# McPiFace-RGBPanel-V1.net
KiCad netlist of a schematic drawn in EAGLE
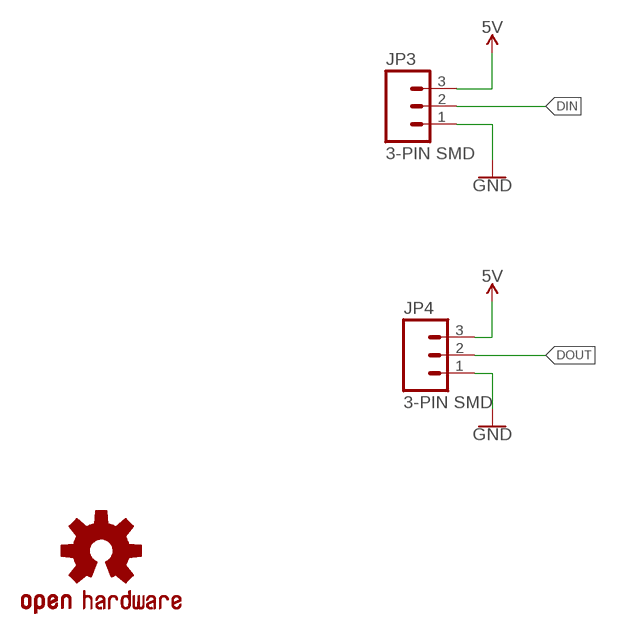
[diagram p0: schematic, sheet 1, part 1 of 2]
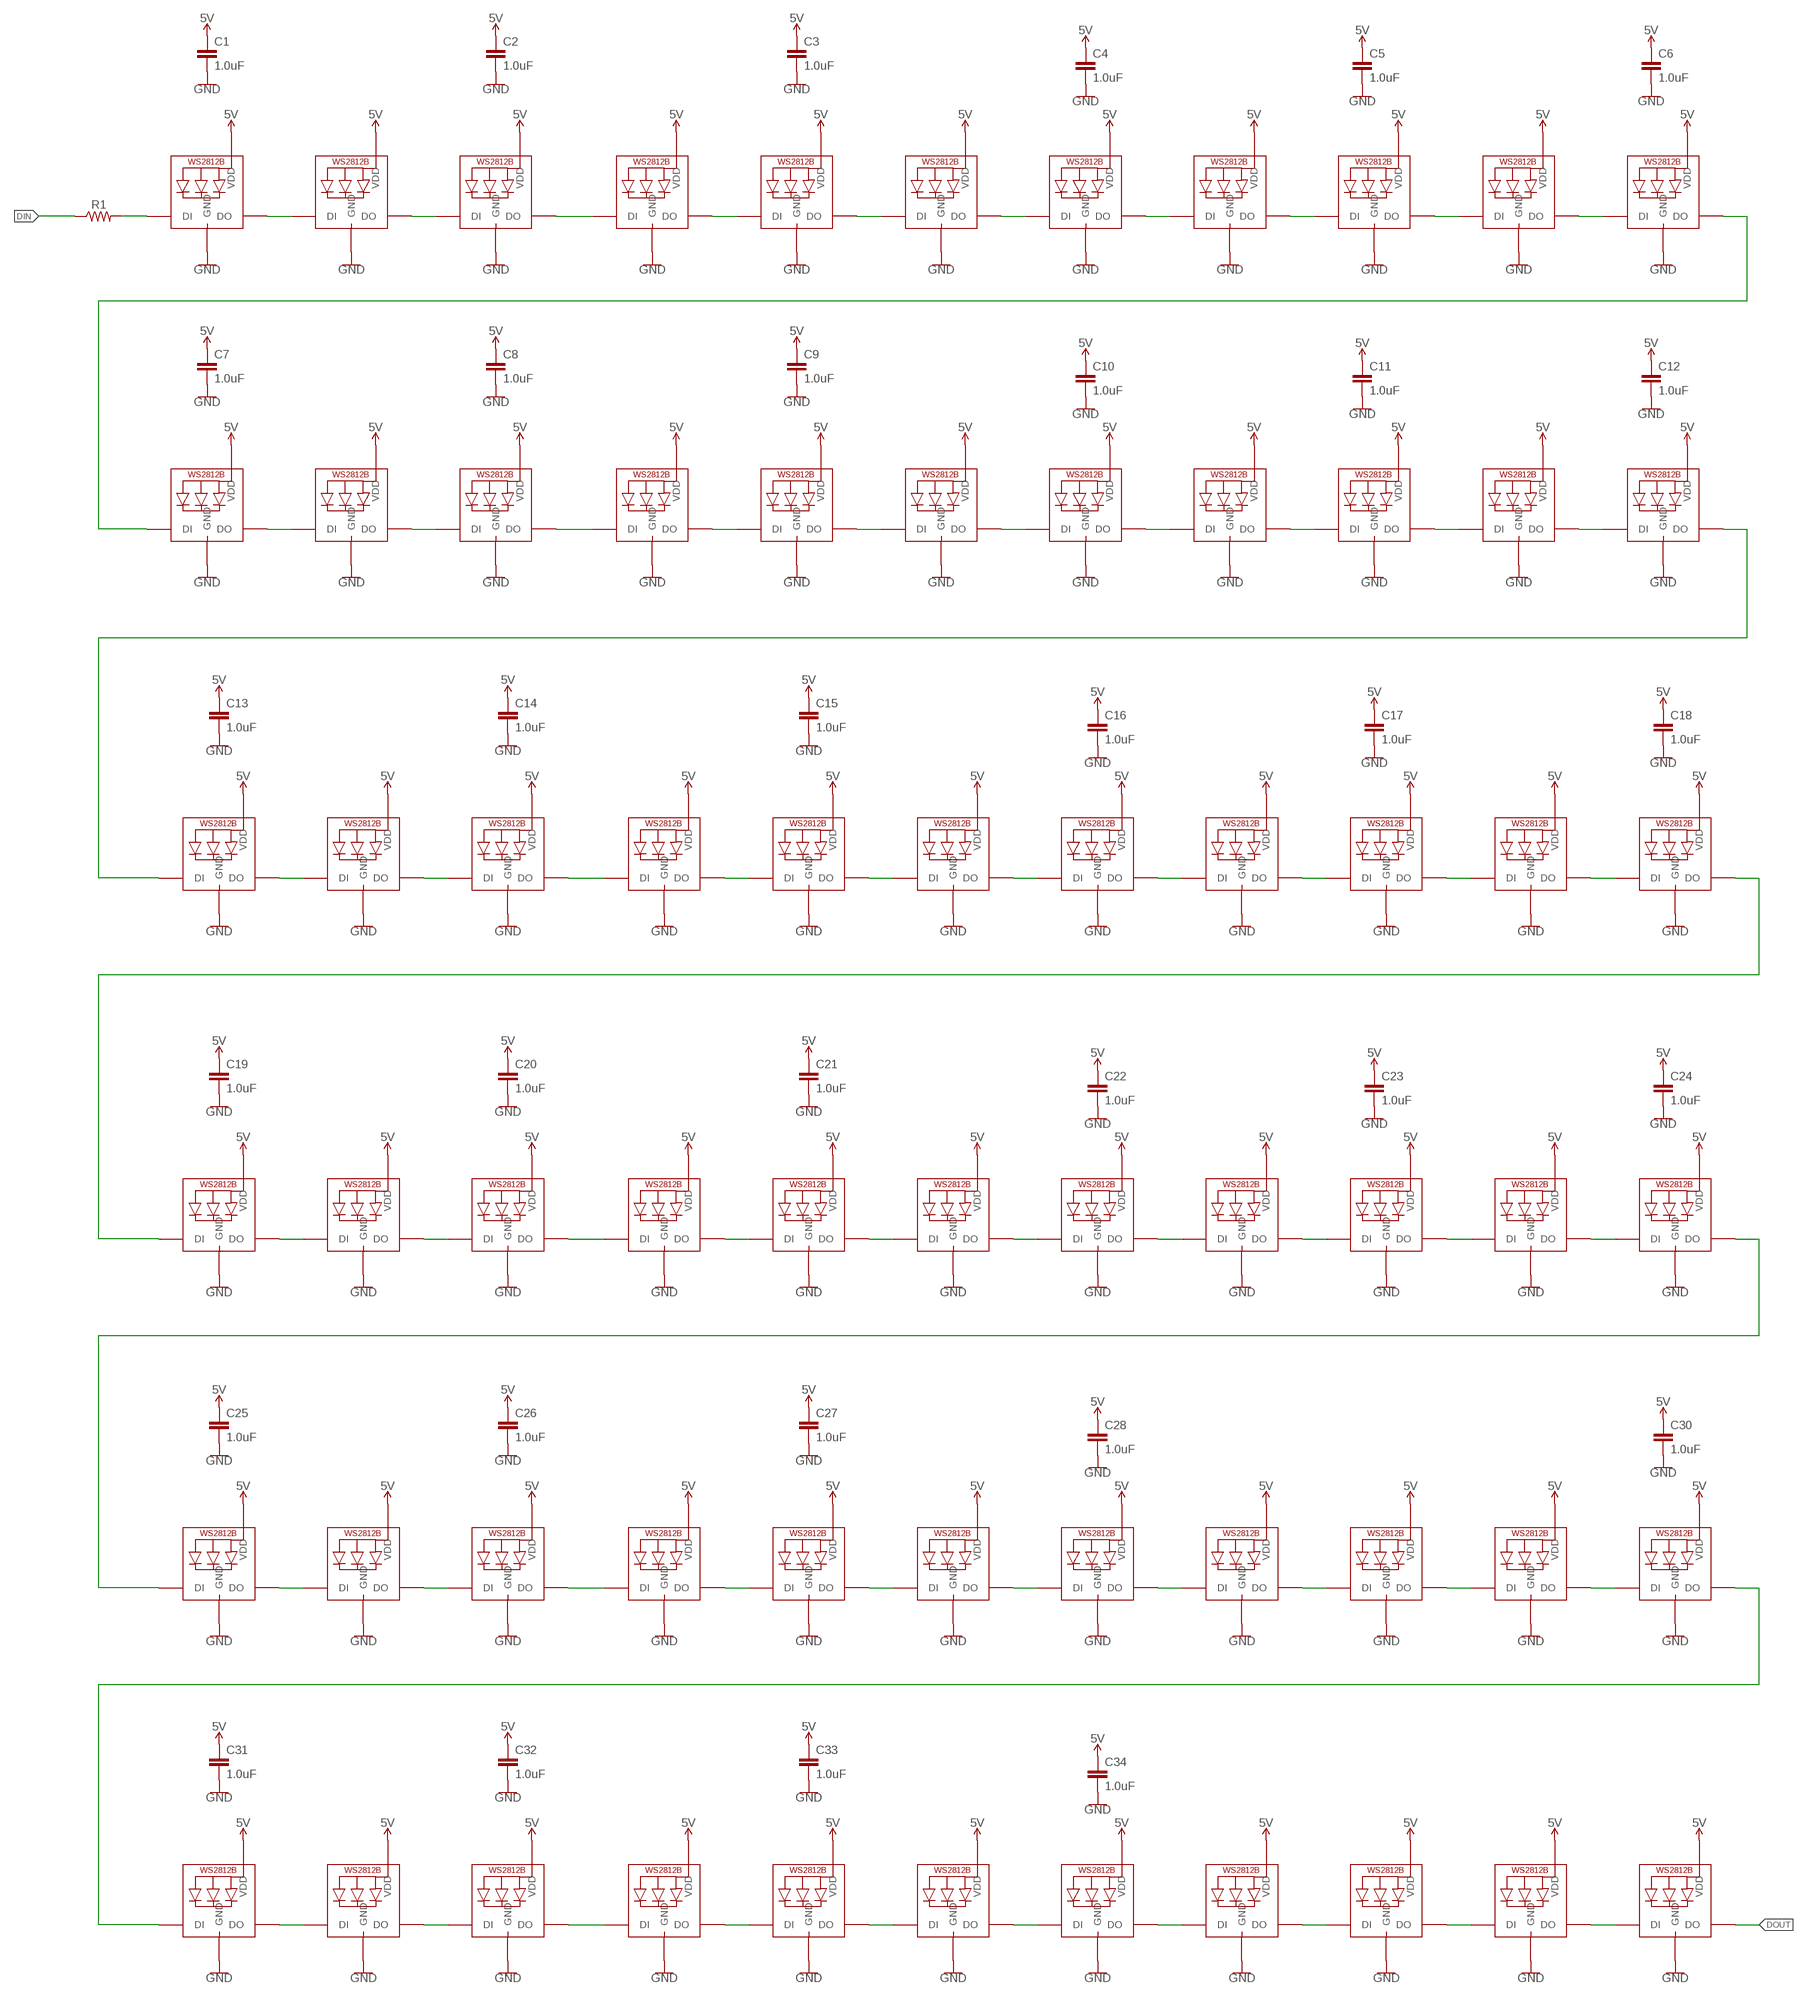
[diagram p1: schematic, sheet 1, part 2 of 2]

(export (version "E")
  (design (tool "Eeschema 10.0.6"))
  (components
    (comp (ref "C1")
      (value "1.0uF")
      (footprint "eagle-import:0805-CAP")
      (libsource (lib "eagle-import") (part "1.0UF-25V-+80/-20(0805){dblquote}"))
    )
    (comp (ref "C2")
      (value "1.0uF")
      (footprint "eagle-import:0805-CAP")
      (libsource (lib "eagle-import") (part "1.0UF-25V-+80/-20(0805){dblquote}"))
    )
    (comp (ref "C3")
      (value "1.0uF")
      (footprint "eagle-import:0805-CAP")
      (libsource (lib "eagle-import") (part "1.0UF-25V-+80/-20(0805){dblquote}"))
    )
    (comp (ref "C4")
      (value "1.0uF")
      (footprint "eagle-import:0805-CAP")
      (libsource (lib "eagle-import") (part "1.0UF-25V-+80/-20(0805){dblquote}"))
    )
    (comp (ref "C5")
      (value "1.0uF")
      (footprint "eagle-import:0805-CAP")
      (libsource (lib "eagle-import") (part "1.0UF-25V-+80/-20(0805){dblquote}"))
    )
    (comp (ref "C6")
      (value "1.0uF")
      (footprint "eagle-import:0805-CAP")
      (libsource (lib "eagle-import") (part "1.0UF-25V-+80/-20(0805){dblquote}"))
    )
    (comp (ref "C7")
      (value "1.0uF")
      (footprint "eagle-import:0805-CAP")
      (libsource (lib "eagle-import") (part "1.0UF-25V-+80/-20(0805){dblquote}"))
    )
    (comp (ref "C8")
      (value "1.0uF")
      (footprint "eagle-import:0805-CAP")
      (libsource (lib "eagle-import") (part "1.0UF-25V-+80/-20(0805){dblquote}"))
    )
    (comp (ref "C9")
      (value "1.0uF")
      (footprint "eagle-import:0805-CAP")
      (libsource (lib "eagle-import") (part "1.0UF-25V-+80/-20(0805){dblquote}"))
    )
    (comp (ref "C10")
      (value "1.0uF")
      (footprint "eagle-import:0805-CAP")
      (libsource (lib "eagle-import") (part "1.0UF-25V-+80/-20(0805){dblquote}"))
    )
    (comp (ref "C11")
      (value "1.0uF")
      (footprint "eagle-import:0805-CAP")
      (libsource (lib "eagle-import") (part "1.0UF-25V-+80/-20(0805){dblquote}"))
    )
    (comp (ref "C12")
      (value "1.0uF")
      (footprint "eagle-import:0805-CAP")
      (libsource (lib "eagle-import") (part "1.0UF-25V-+80/-20(0805){dblquote}"))
    )
    (comp (ref "C13")
      (value "1.0uF")
      (footprint "eagle-import:0805-CAP")
      (libsource (lib "eagle-import") (part "1.0UF-25V-+80/-20(0805){dblquote}"))
    )
    (comp (ref "C14")
      (value "1.0uF")
      (footprint "eagle-import:0805-CAP")
      (libsource (lib "eagle-import") (part "1.0UF-25V-+80/-20(0805){dblquote}"))
    )
    (comp (ref "C15")
      (value "1.0uF")
      (footprint "eagle-import:0805-CAP")
      (libsource (lib "eagle-import") (part "1.0UF-25V-+80/-20(0805){dblquote}"))
    )
    (comp (ref "C16")
      (value "1.0uF")
      (footprint "eagle-import:0805-CAP")
      (libsource (lib "eagle-import") (part "1.0UF-25V-+80/-20(0805){dblquote}"))
    )
    (comp (ref "C17")
      (value "1.0uF")
      (footprint "eagle-import:0805-CAP")
      (libsource (lib "eagle-import") (part "1.0UF-25V-+80/-20(0805){dblquote}"))
    )
    (comp (ref "C18")
      (value "1.0uF")
      (footprint "eagle-import:0805-CAP")
      (libsource (lib "eagle-import") (part "1.0UF-25V-+80/-20(0805){dblquote}"))
    )
    (comp (ref "C19")
      (value "1.0uF")
      (footprint "eagle-import:0805-CAP")
      (libsource (lib "eagle-import") (part "1.0UF-25V-+80/-20(0805){dblquote}"))
    )
    (comp (ref "C20")
      (value "1.0uF")
      (footprint "eagle-import:0805-CAP")
      (libsource (lib "eagle-import") (part "1.0UF-25V-+80/-20(0805){dblquote}"))
    )
    (comp (ref "C21")
      (value "1.0uF")
      (footprint "eagle-import:0805-CAP")
      (libsource (lib "eagle-import") (part "1.0UF-25V-+80/-20(0805){dblquote}"))
    )
    (comp (ref "C22")
      (value "1.0uF")
      (footprint "eagle-import:0805-CAP")
      (libsource (lib "eagle-import") (part "1.0UF-25V-+80/-20(0805){dblquote}"))
    )
    (comp (ref "C23")
      (value "1.0uF")
      (footprint "eagle-import:0805-CAP")
      (libsource (lib "eagle-import") (part "1.0UF-25V-+80/-20(0805){dblquote}"))
    )
    (comp (ref "C24")
      (value "1.0uF")
      (footprint "eagle-import:0805-CAP")
      (libsource (lib "eagle-import") (part "1.0UF-25V-+80/-20(0805){dblquote}"))
    )
    (comp (ref "C25")
      (value "1.0uF")
      (footprint "eagle-import:0805-CAP")
      (libsource (lib "eagle-import") (part "1.0UF-25V-+80/-20(0805){dblquote}"))
    )
    (comp (ref "C26")
      (value "1.0uF")
      (footprint "eagle-import:0805-CAP")
      (libsource (lib "eagle-import") (part "1.0UF-25V-+80/-20(0805){dblquote}"))
    )
    (comp (ref "C27")
      (value "1.0uF")
      (footprint "eagle-import:0805-CAP")
      (libsource (lib "eagle-import") (part "1.0UF-25V-+80/-20(0805){dblquote}"))
    )
    (comp (ref "C28")
      (value "1.0uF")
      (footprint "eagle-import:0805-CAP")
      (libsource (lib "eagle-import") (part "1.0UF-25V-+80/-20(0805){dblquote}"))
    )
    (comp (ref "C30")
      (value "1.0uF")
      (footprint "eagle-import:0805-CAP")
      (libsource (lib "eagle-import") (part "1.0UF-25V-+80/-20(0805){dblquote}"))
    )
    (comp (ref "C31")
      (value "1.0uF")
      (footprint "eagle-import:0805-CAP")
      (libsource (lib "eagle-import") (part "1.0UF-25V-+80/-20(0805){dblquote}"))
    )
    (comp (ref "C32")
      (value "1.0uF")
      (footprint "eagle-import:0805-CAP")
      (libsource (lib "eagle-import") (part "1.0UF-25V-+80/-20(0805){dblquote}"))
    )
    (comp (ref "C33")
      (value "1.0uF")
      (footprint "eagle-import:0805-CAP")
      (libsource (lib "eagle-import") (part "1.0UF-25V-+80/-20(0805){dblquote}"))
    )
    (comp (ref "C34")
      (value "1.0uF")
      (footprint "eagle-import:0805-CAP")
      (libsource (lib "eagle-import") (part "1.0UF-25V-+80/-20(0805){dblquote}"))
    )
    (comp (ref "JP3")
      (value "3-PIN SMD")
      (footprint "eagle-import:JST-3-SMD")
      (libsource (lib "eagle-import") (part "M03JST-SMD"))
    )
    (comp (ref "JP4")
      (value "3-PIN SMD")
      (footprint "eagle-import:JST-3-SMD")
      (libsource (lib "eagle-import") (part "M03JST-SMD"))
    )
    (comp (ref "LED1")
      (value "WS2812B5050")
      (footprint "eagle-import:WS2812B")
      (libsource (lib "eagle-import") (part "WS2812B5050"))
    )
    (comp (ref "LED2")
      (value "WS2812B5050")
      (footprint "eagle-import:WS2812B")
      (libsource (lib "eagle-import") (part "WS2812B5050"))
    )
    (comp (ref "LED3")
      (value "WS2812B5050")
      (footprint "eagle-import:WS2812B")
      (libsource (lib "eagle-import") (part "WS2812B5050"))
    )
    (comp (ref "LED4")
      (value "WS2812B5050")
      (footprint "eagle-import:WS2812B")
      (libsource (lib "eagle-import") (part "WS2812B5050"))
    )
    (comp (ref "LED5")
      (value "WS2812B5050")
      (footprint "eagle-import:WS2812B")
      (libsource (lib "eagle-import") (part "WS2812B5050"))
    )
    (comp (ref "LED6")
      (value "WS2812B5050")
      (footprint "eagle-import:WS2812B")
      (libsource (lib "eagle-import") (part "WS2812B5050"))
    )
    (comp (ref "LED7")
      (value "WS2812B5050")
      (footprint "eagle-import:WS2812B")
      (libsource (lib "eagle-import") (part "WS2812B5050"))
    )
    (comp (ref "LED8")
      (value "WS2812B5050")
      (footprint "eagle-import:WS2812B")
      (libsource (lib "eagle-import") (part "WS2812B5050"))
    )
    (comp (ref "LED9")
      (value "WS2812B5050")
      (footprint "eagle-import:WS2812B")
      (libsource (lib "eagle-import") (part "WS2812B5050"))
    )
    (comp (ref "LED10")
      (value "WS2812B5050")
      (footprint "eagle-import:WS2812B")
      (libsource (lib "eagle-import") (part "WS2812B5050"))
    )
    (comp (ref "LED11")
      (value "WS2812B5050")
      (footprint "eagle-import:WS2812B")
      (libsource (lib "eagle-import") (part "WS2812B5050"))
    )
    (comp (ref "LED12")
      (value "WS2812B5050")
      (footprint "eagle-import:WS2812B")
      (libsource (lib "eagle-import") (part "WS2812B5050"))
    )
    (comp (ref "LED13")
      (value "WS2812B5050")
      (footprint "eagle-import:WS2812B")
      (libsource (lib "eagle-import") (part "WS2812B5050"))
    )
    (comp (ref "LED14")
      (value "WS2812B5050")
      (footprint "eagle-import:WS2812B")
      (libsource (lib "eagle-import") (part "WS2812B5050"))
    )
    (comp (ref "LED15")
      (value "WS2812B5050")
      (footprint "eagle-import:WS2812B")
      (libsource (lib "eagle-import") (part "WS2812B5050"))
    )
    (comp (ref "LED16")
      (value "WS2812B5050")
      (footprint "eagle-import:WS2812B")
      (libsource (lib "eagle-import") (part "WS2812B5050"))
    )
    (comp (ref "LED17")
      (value "WS2812B5050")
      (footprint "eagle-import:WS2812B")
      (libsource (lib "eagle-import") (part "WS2812B5050"))
    )
    (comp (ref "LED18")
      (value "WS2812B5050")
      (footprint "eagle-import:WS2812B")
      (libsource (lib "eagle-import") (part "WS2812B5050"))
    )
    (comp (ref "LED19")
      (value "WS2812B5050")
      (footprint "eagle-import:WS2812B")
      (libsource (lib "eagle-import") (part "WS2812B5050"))
    )
    (comp (ref "LED20")
      (value "WS2812B5050")
      (footprint "eagle-import:WS2812B")
      (libsource (lib "eagle-import") (part "WS2812B5050"))
    )
    (comp (ref "LED21")
      (value "WS2812B5050")
      (footprint "eagle-import:WS2812B")
      (libsource (lib "eagle-import") (part "WS2812B5050"))
    )
    (comp (ref "LED22")
      (value "WS2812B5050")
      (footprint "eagle-import:WS2812B")
      (libsource (lib "eagle-import") (part "WS2812B5050"))
    )
    (comp (ref "LED23")
      (value "WS2812B5050")
      (footprint "eagle-import:WS2812B")
      (libsource (lib "eagle-import") (part "WS2812B5050"))
    )
    (comp (ref "LED24")
      (value "WS2812B5050")
      (footprint "eagle-import:WS2812B")
      (libsource (lib "eagle-import") (part "WS2812B5050"))
    )
    (comp (ref "LED25")
      (value "WS2812B5050")
      (footprint "eagle-import:WS2812B")
      (libsource (lib "eagle-import") (part "WS2812B5050"))
    )
    (comp (ref "LED26")
      (value "WS2812B5050")
      (footprint "eagle-import:WS2812B")
      (libsource (lib "eagle-import") (part "WS2812B5050"))
    )
    (comp (ref "LED27")
      (value "WS2812B5050")
      (footprint "eagle-import:WS2812B")
      (libsource (lib "eagle-import") (part "WS2812B5050"))
    )
    (comp (ref "LED28")
      (value "WS2812B5050")
      (footprint "eagle-import:WS2812B")
      (libsource (lib "eagle-import") (part "WS2812B5050"))
    )
    (comp (ref "LED29")
      (value "WS2812B5050")
      (footprint "eagle-import:WS2812B")
      (libsource (lib "eagle-import") (part "WS2812B5050"))
    )
    (comp (ref "LED30")
      (value "WS2812B5050")
      (footprint "eagle-import:WS2812B")
      (libsource (lib "eagle-import") (part "WS2812B5050"))
    )
    (comp (ref "LED31")
      (value "WS2812B5050")
      (footprint "eagle-import:WS2812B")
      (libsource (lib "eagle-import") (part "WS2812B5050"))
    )
    (comp (ref "LED32")
      (value "WS2812B5050")
      (footprint "eagle-import:WS2812B")
      (libsource (lib "eagle-import") (part "WS2812B5050"))
    )
    (comp (ref "LED33")
      (value "WS2812B5050")
      (footprint "eagle-import:WS2812B")
      (libsource (lib "eagle-import") (part "WS2812B5050"))
    )
    (comp (ref "LED34")
      (value "WS2812B5050")
      (footprint "eagle-import:WS2812B")
      (libsource (lib "eagle-import") (part "WS2812B5050"))
    )
    (comp (ref "LED35")
      (value "WS2812B5050")
      (footprint "eagle-import:WS2812B")
      (libsource (lib "eagle-import") (part "WS2812B5050"))
    )
    (comp (ref "LED36")
      (value "WS2812B5050")
      (footprint "eagle-import:WS2812B")
      (libsource (lib "eagle-import") (part "WS2812B5050"))
    )
    (comp (ref "LED37")
      (value "WS2812B5050")
      (footprint "eagle-import:WS2812B")
      (libsource (lib "eagle-import") (part "WS2812B5050"))
    )
    (comp (ref "LED38")
      (value "WS2812B5050")
      (footprint "eagle-import:WS2812B")
      (libsource (lib "eagle-import") (part "WS2812B5050"))
    )
    (comp (ref "LED39")
      (value "WS2812B5050")
      (footprint "eagle-import:WS2812B")
      (libsource (lib "eagle-import") (part "WS2812B5050"))
    )
    (comp (ref "LED40")
      (value "WS2812B5050")
      (footprint "eagle-import:WS2812B")
      (libsource (lib "eagle-import") (part "WS2812B5050"))
    )
    (comp (ref "LED41")
      (value "WS2812B5050")
      (footprint "eagle-import:WS2812B")
      (libsource (lib "eagle-import") (part "WS2812B5050"))
    )
    (comp (ref "LED42")
      (value "WS2812B5050")
      (footprint "eagle-import:WS2812B")
      (libsource (lib "eagle-import") (part "WS2812B5050"))
    )
    (comp (ref "LED43")
      (value "WS2812B5050")
      (footprint "eagle-import:WS2812B")
      (libsource (lib "eagle-import") (part "WS2812B5050"))
    )
    (comp (ref "LED44")
      (value "WS2812B5050")
      (footprint "eagle-import:WS2812B")
      (libsource (lib "eagle-import") (part "WS2812B5050"))
    )
    (comp (ref "LED45")
      (value "WS2812B5050")
      (footprint "eagle-import:WS2812B")
      (libsource (lib "eagle-import") (part "WS2812B5050"))
    )
    (comp (ref "LED46")
      (value "WS2812B5050")
      (footprint "eagle-import:WS2812B")
      (libsource (lib "eagle-import") (part "WS2812B5050"))
    )
    (comp (ref "LED47")
      (value "WS2812B5050")
      (footprint "eagle-import:WS2812B")
      (libsource (lib "eagle-import") (part "WS2812B5050"))
    )
    (comp (ref "LED48")
      (value "WS2812B5050")
      (footprint "eagle-import:WS2812B")
      (libsource (lib "eagle-import") (part "WS2812B5050"))
    )
    (comp (ref "LED49")
      (value "WS2812B5050")
      (footprint "eagle-import:WS2812B")
      (libsource (lib "eagle-import") (part "WS2812B5050"))
    )
    (comp (ref "LED50")
      (value "WS2812B5050")
      (footprint "eagle-import:WS2812B")
      (libsource (lib "eagle-import") (part "WS2812B5050"))
    )
    (comp (ref "LED51")
      (value "WS2812B5050")
      (footprint "eagle-import:WS2812B")
      (libsource (lib "eagle-import") (part "WS2812B5050"))
    )
    (comp (ref "LED52")
      (value "WS2812B5050")
      (footprint "eagle-import:WS2812B")
      (libsource (lib "eagle-import") (part "WS2812B5050"))
    )
    (comp (ref "LED53")
      (value "WS2812B5050")
      (footprint "eagle-import:WS2812B")
      (libsource (lib "eagle-import") (part "WS2812B5050"))
    )
    (comp (ref "LED54")
      (value "WS2812B5050")
      (footprint "eagle-import:WS2812B")
      (libsource (lib "eagle-import") (part "WS2812B5050"))
    )
    (comp (ref "LED55")
      (value "WS2812B5050")
      (footprint "eagle-import:WS2812B")
      (libsource (lib "eagle-import") (part "WS2812B5050"))
    )
    (comp (ref "LED56")
      (value "WS2812B5050")
      (footprint "eagle-import:WS2812B")
      (libsource (lib "eagle-import") (part "WS2812B5050"))
    )
    (comp (ref "LED57")
      (value "WS2812B5050")
      (footprint "eagle-import:WS2812B")
      (libsource (lib "eagle-import") (part "WS2812B5050"))
    )
    (comp (ref "LED58")
      (value "WS2812B5050")
      (footprint "eagle-import:WS2812B")
      (libsource (lib "eagle-import") (part "WS2812B5050"))
    )
    (comp (ref "LED59")
      (value "WS2812B5050")
      (footprint "eagle-import:WS2812B")
      (libsource (lib "eagle-import") (part "WS2812B5050"))
    )
    (comp (ref "LED60")
      (value "WS2812B5050")
      (footprint "eagle-import:WS2812B")
      (libsource (lib "eagle-import") (part "WS2812B5050"))
    )
    (comp (ref "LED61")
      (value "WS2812B5050")
      (footprint "eagle-import:WS2812B")
      (libsource (lib "eagle-import") (part "WS2812B5050"))
    )
    (comp (ref "LED62")
      (value "WS2812B5050")
      (footprint "eagle-import:WS2812B")
      (libsource (lib "eagle-import") (part "WS2812B5050"))
    )
    (comp (ref "LED63")
      (value "WS2812B5050")
      (footprint "eagle-import:WS2812B")
      (libsource (lib "eagle-import") (part "WS2812B5050"))
    )
    (comp (ref "LED64")
      (value "WS2812B5050")
      (footprint "eagle-import:WS2812B")
      (libsource (lib "eagle-import") (part "WS2812B5050"))
    )
    (comp (ref "LED65")
      (value "WS2812B5050")
      (footprint "eagle-import:WS2812B")
      (libsource (lib "eagle-import") (part "WS2812B5050"))
    )
    (comp (ref "LED66")
      (value "WS2812B5050")
      (footprint "eagle-import:WS2812B")
      (libsource (lib "eagle-import") (part "WS2812B5050"))
    )
    (comp (ref "LOGO1")
      (value "OSHW-LOGOL")
      (footprint "eagle-import:OSHW-LOGO-L")
      (libsource (lib "eagle-import") (part "OSHW-LOGOL"))
    )
    (comp (ref "R1")
      (value "RESISTOR0805")
      (footprint "eagle-import:0805")
      (libsource (lib "eagle-import") (part "RESISTOR0805"))
    )
  )
  (nets
    (net (code "1") (name "5V") (class "Default")
      (node (ref "C1") (pin "1") (pinfunction "1_1") (pintype "passive"))
      (node (ref "C10") (pin "1") (pinfunction "1_1") (pintype "passive"))
      (node (ref "C11") (pin "1") (pinfunction "1_1") (pintype "passive"))
      (node (ref "C12") (pin "1") (pinfunction "1_1") (pintype "passive"))
      (node (ref "C13") (pin "1") (pinfunction "1_1") (pintype "passive"))
      (node (ref "C14") (pin "1") (pinfunction "1_1") (pintype "passive"))
      (node (ref "C15") (pin "1") (pinfunction "1_1") (pintype "passive"))
      (node (ref "C16") (pin "1") (pinfunction "1_1") (pintype "passive"))
      (node (ref "C17") (pin "1") (pinfunction "1_1") (pintype "passive"))
      (node (ref "C18") (pin "1") (pinfunction "1_1") (pintype "passive"))
      (node (ref "C19") (pin "1") (pinfunction "1_1") (pintype "passive"))
      (node (ref "C2") (pin "1") (pinfunction "1_1") (pintype "passive"))
      (node (ref "C20") (pin "1") (pinfunction "1_1") (pintype "passive"))
      (node (ref "C21") (pin "1") (pinfunction "1_1") (pintype "passive"))
      (node (ref "C22") (pin "1") (pinfunction "1_1") (pintype "passive"))
      (node (ref "C23") (pin "1") (pinfunction "1_1") (pintype "passive"))
      (node (ref "C24") (pin "1") (pinfunction "1_1") (pintype "passive"))
      (node (ref "C25") (pin "1") (pinfunction "1_1") (pintype "passive"))
      (node (ref "C26") (pin "1") (pinfunction "1_1") (pintype "passive"))
      (node (ref "C27") (pin "1") (pinfunction "1_1") (pintype "passive"))
      (node (ref "C28") (pin "1") (pinfunction "1_1") (pintype "passive"))
      (node (ref "C3") (pin "1") (pinfunction "1_1") (pintype "passive"))
      (node (ref "C30") (pin "1") (pinfunction "1_1") (pintype "passive"))
      (node (ref "C31") (pin "1") (pinfunction "1_1") (pintype "passive"))
      (node (ref "C32") (pin "1") (pinfunction "1_1") (pintype "passive"))
      (node (ref "C33") (pin "1") (pinfunction "1_1") (pintype "passive"))
      (node (ref "C34") (pin "1") (pinfunction "1_1") (pintype "passive"))
      (node (ref "C4") (pin "1") (pinfunction "1_1") (pintype "passive"))
      (node (ref "C5") (pin "1") (pinfunction "1_1") (pintype "passive"))
      (node (ref "C6") (pin "1") (pinfunction "1_1") (pintype "passive"))
      (node (ref "C7") (pin "1") (pinfunction "1_1") (pintype "passive"))
      (node (ref "C8") (pin "1") (pinfunction "1_1") (pintype "passive"))
      (node (ref "C9") (pin "1") (pinfunction "1_1") (pintype "passive"))
      (node (ref "JP3") (pin "3") (pinfunction "3_3") (pintype "passive"))
      (node (ref "JP4") (pin "3") (pinfunction "3_3") (pintype "passive"))
      (node (ref "LED1") (pin "1-VDD") (pinfunction "VDD_1-VDD") (pintype "power_in"))
      (node (ref "LED10") (pin "1-VDD") (pinfunction "VDD_1-VDD") (pintype "power_in"))
      (node (ref "LED11") (pin "1-VDD") (pinfunction "VDD_1-VDD") (pintype "power_in"))
      (node (ref "LED12") (pin "1-VDD") (pinfunction "VDD_1-VDD") (pintype "power_in"))
      (node (ref "LED13") (pin "1-VDD") (pinfunction "VDD_1-VDD") (pintype "power_in"))
      (node (ref "LED14") (pin "1-VDD") (pinfunction "VDD_1-VDD") (pintype "power_in"))
      (node (ref "LED15") (pin "1-VDD") (pinfunction "VDD_1-VDD") (pintype "power_in"))
      (node (ref "LED16") (pin "1-VDD") (pinfunction "VDD_1-VDD") (pintype "power_in"))
      (node (ref "LED17") (pin "1-VDD") (pinfunction "VDD_1-VDD") (pintype "power_in"))
      (node (ref "LED18") (pin "1-VDD") (pinfunction "VDD_1-VDD") (pintype "power_in"))
      (node (ref "LED19") (pin "1-VDD") (pinfunction "VDD_1-VDD") (pintype "power_in"))
      (node (ref "LED2") (pin "1-VDD") (pinfunction "VDD_1-VDD") (pintype "power_in"))
      (node (ref "LED20") (pin "1-VDD") (pinfunction "VDD_1-VDD") (pintype "power_in"))
      (node (ref "LED21") (pin "1-VDD") (pinfunction "VDD_1-VDD") (pintype "power_in"))
      (node (ref "LED22") (pin "1-VDD") (pinfunction "VDD_1-VDD") (pintype "power_in"))
      (node (ref "LED23") (pin "1-VDD") (pinfunction "VDD_1-VDD") (pintype "power_in"))
      (node (ref "LED24") (pin "1-VDD") (pinfunction "VDD_1-VDD") (pintype "power_in"))
      (node (ref "LED25") (pin "1-VDD") (pinfunction "VDD_1-VDD") (pintype "power_in"))
      (node (ref "LED26") (pin "1-VDD") (pinfunction "VDD_1-VDD") (pintype "power_in"))
      (node (ref "LED27") (pin "1-VDD") (pinfunction "VDD_1-VDD") (pintype "power_in"))
      (node (ref "LED28") (pin "1-VDD") (pinfunction "VDD_1-VDD") (pintype "power_in"))
      (node (ref "LED29") (pin "1-VDD") (pinfunction "VDD_1-VDD") (pintype "power_in"))
      (node (ref "LED3") (pin "1-VDD") (pinfunction "VDD_1-VDD") (pintype "power_in"))
      (node (ref "LED30") (pin "1-VDD") (pinfunction "VDD_1-VDD") (pintype "power_in"))
      (node (ref "LED31") (pin "1-VDD") (pinfunction "VDD_1-VDD") (pintype "power_in"))
      (node (ref "LED32") (pin "1-VDD") (pinfunction "VDD_1-VDD") (pintype "power_in"))
      (node (ref "LED33") (pin "1-VDD") (pinfunction "VDD_1-VDD") (pintype "power_in"))
      (node (ref "LED34") (pin "1-VDD") (pinfunction "VDD_1-VDD") (pintype "power_in"))
      (node (ref "LED35") (pin "1-VDD") (pinfunction "VDD_1-VDD") (pintype "power_in"))
      (node (ref "LED36") (pin "1-VDD") (pinfunction "VDD_1-VDD") (pintype "power_in"))
      (node (ref "LED37") (pin "1-VDD") (pinfunction "VDD_1-VDD") (pintype "power_in"))
      (node (ref "LED38") (pin "1-VDD") (pinfunction "VDD_1-VDD") (pintype "power_in"))
      (node (ref "LED39") (pin "1-VDD") (pinfunction "VDD_1-VDD") (pintype "power_in"))
      (node (ref "LED4") (pin "1-VDD") (pinfunction "VDD_1-VDD") (pintype "power_in"))
      (node (ref "LED40") (pin "1-VDD") (pinfunction "VDD_1-VDD") (pintype "power_in"))
      (node (ref "LED41") (pin "1-VDD") (pinfunction "VDD_1-VDD") (pintype "power_in"))
      (node (ref "LED42") (pin "1-VDD") (pinfunction "VDD_1-VDD") (pintype "power_in"))
      (node (ref "LED43") (pin "1-VDD") (pinfunction "VDD_1-VDD") (pintype "power_in"))
      (node (ref "LED44") (pin "1-VDD") (pinfunction "VDD_1-VDD") (pintype "power_in"))
      (node (ref "LED45") (pin "1-VDD") (pinfunction "VDD_1-VDD") (pintype "power_in"))
      (node (ref "LED46") (pin "1-VDD") (pinfunction "VDD_1-VDD") (pintype "power_in"))
      (node (ref "LED47") (pin "1-VDD") (pinfunction "VDD_1-VDD") (pintype "power_in"))
      (node (ref "LED48") (pin "1-VDD") (pinfunction "VDD_1-VDD") (pintype "power_in"))
      (node (ref "LED49") (pin "1-VDD") (pinfunction "VDD_1-VDD") (pintype "power_in"))
      (node (ref "LED5") (pin "1-VDD") (pinfunction "VDD_1-VDD") (pintype "power_in"))
      (node (ref "LED50") (pin "1-VDD") (pinfunction "VDD_1-VDD") (pintype "power_in"))
      (node (ref "LED51") (pin "1-VDD") (pinfunction "VDD_1-VDD") (pintype "power_in"))
      (node (ref "LED52") (pin "1-VDD") (pinfunction "VDD_1-VDD") (pintype "power_in"))
      (node (ref "LED53") (pin "1-VDD") (pinfunction "VDD_1-VDD") (pintype "power_in"))
      (node (ref "LED54") (pin "1-VDD") (pinfunction "VDD_1-VDD") (pintype "power_in"))
      (node (ref "LED55") (pin "1-VDD") (pinfunction "VDD_1-VDD") (pintype "power_in"))
      (node (ref "LED56") (pin "1-VDD") (pinfunction "VDD_1-VDD") (pintype "power_in"))
      (node (ref "LED57") (pin "1-VDD") (pinfunction "VDD_1-VDD") (pintype "power_in"))
      (node (ref "LED58") (pin "1-VDD") (pinfunction "VDD_1-VDD") (pintype "power_in"))
      (node (ref "LED59") (pin "1-VDD") (pinfunction "VDD_1-VDD") (pintype "power_in"))
      (node (ref "LED6") (pin "1-VDD") (pinfunction "VDD_1-VDD") (pintype "power_in"))
      (node (ref "LED60") (pin "1-VDD") (pinfunction "VDD_1-VDD") (pintype "power_in"))
      (node (ref "LED61") (pin "1-VDD") (pinfunction "VDD_1-VDD") (pintype "power_in"))
      (node (ref "LED62") (pin "1-VDD") (pinfunction "VDD_1-VDD") (pintype "power_in"))
      (node (ref "LED63") (pin "1-VDD") (pinfunction "VDD_1-VDD") (pintype "power_in"))
      (node (ref "LED64") (pin "1-VDD") (pinfunction "VDD_1-VDD") (pintype "power_in"))
      (node (ref "LED65") (pin "1-VDD") (pinfunction "VDD_1-VDD") (pintype "power_in"))
      (node (ref "LED66") (pin "1-VDD") (pinfunction "VDD_1-VDD") (pintype "power_in"))
      (node (ref "LED7") (pin "1-VDD") (pinfunction "VDD_1-VDD") (pintype "power_in"))
      (node (ref "LED8") (pin "1-VDD") (pinfunction "VDD_1-VDD") (pintype "power_in"))
      (node (ref "LED9") (pin "1-VDD") (pinfunction "VDD_1-VDD") (pintype "power_in"))
    )
    (net (code "2") (name "DIN") (class "Default")
      (node (ref "JP3") (pin "2") (pinfunction "2_2") (pintype "passive"))
      (node (ref "R1") (pin "1") (pinfunction "1_1") (pintype "passive"))
    )
    (net (code "3") (name "DOUT") (class "Default")
      (node (ref "JP4") (pin "2") (pinfunction "2_2") (pintype "passive"))
      (node (ref "LED66") (pin "2-DOUT") (pinfunction "DO_2-DOUT") (pintype "output"))
    )
    (net (code "4") (name "GND") (class "Default")
      (node (ref "C1") (pin "2") (pinfunction "2_2") (pintype "passive"))
      (node (ref "C10") (pin "2") (pinfunction "2_2") (pintype "passive"))
      (node (ref "C11") (pin "2") (pinfunction "2_2") (pintype "passive"))
      (node (ref "C12") (pin "2") (pinfunction "2_2") (pintype "passive"))
      (node (ref "C13") (pin "2") (pinfunction "2_2") (pintype "passive"))
      (node (ref "C14") (pin "2") (pinfunction "2_2") (pintype "passive"))
      (node (ref "C15") (pin "2") (pinfunction "2_2") (pintype "passive"))
      (node (ref "C16") (pin "2") (pinfunction "2_2") (pintype "passive"))
      (node (ref "C17") (pin "2") (pinfunction "2_2") (pintype "passive"))
      (node (ref "C18") (pin "2") (pinfunction "2_2") (pintype "passive"))
      (node (ref "C19") (pin "2") (pinfunction "2_2") (pintype "passive"))
      (node (ref "C2") (pin "2") (pinfunction "2_2") (pintype "passive"))
      (node (ref "C20") (pin "2") (pinfunction "2_2") (pintype "passive"))
      (node (ref "C21") (pin "2") (pinfunction "2_2") (pintype "passive"))
      (node (ref "C22") (pin "2") (pinfunction "2_2") (pintype "passive"))
      (node (ref "C23") (pin "2") (pinfunction "2_2") (pintype "passive"))
      (node (ref "C24") (pin "2") (pinfunction "2_2") (pintype "passive"))
      (node (ref "C25") (pin "2") (pinfunction "2_2") (pintype "passive"))
      (node (ref "C26") (pin "2") (pinfunction "2_2") (pintype "passive"))
      (node (ref "C27") (pin "2") (pinfunction "2_2") (pintype "passive"))
      (node (ref "C28") (pin "2") (pinfunction "2_2") (pintype "passive"))
      (node (ref "C3") (pin "2") (pinfunction "2_2") (pintype "passive"))
      (node (ref "C30") (pin "2") (pinfunction "2_2") (pintype "passive"))
      (node (ref "C31") (pin "2") (pinfunction "2_2") (pintype "passive"))
      (node (ref "C32") (pin "2") (pinfunction "2_2") (pintype "passive"))
      (node (ref "C33") (pin "2") (pinfunction "2_2") (pintype "passive"))
      (node (ref "C34") (pin "2") (pinfunction "2_2") (pintype "passive"))
      (node (ref "C4") (pin "2") (pinfunction "2_2") (pintype "passive"))
      (node (ref "C5") (pin "2") (pinfunction "2_2") (pintype "passive"))
      (node (ref "C6") (pin "2") (pinfunction "2_2") (pintype "passive"))
      (node (ref "C7") (pin "2") (pinfunction "2_2") (pintype "passive"))
      (node (ref "C8") (pin "2") (pinfunction "2_2") (pintype "passive"))
      (node (ref "C9") (pin "2") (pinfunction "2_2") (pintype "passive"))
      (node (ref "JP3") (pin "1") (pinfunction "1_1") (pintype "passive"))
      (node (ref "JP4") (pin "1") (pinfunction "1_1") (pintype "passive"))
      (node (ref "LED1") (pin "3-GND") (pinfunction "GND_3-GND") (pintype "power_in"))
      (node (ref "LED10") (pin "3-GND") (pinfunction "GND_3-GND") (pintype "power_in"))
      (node (ref "LED11") (pin "3-GND") (pinfunction "GND_3-GND") (pintype "power_in"))
      (node (ref "LED12") (pin "3-GND") (pinfunction "GND_3-GND") (pintype "power_in"))
      (node (ref "LED13") (pin "3-GND") (pinfunction "GND_3-GND") (pintype "power_in"))
      (node (ref "LED14") (pin "3-GND") (pinfunction "GND_3-GND") (pintype "power_in"))
      (node (ref "LED15") (pin "3-GND") (pinfunction "GND_3-GND") (pintype "power_in"))
      (node (ref "LED16") (pin "3-GND") (pinfunction "GND_3-GND") (pintype "power_in"))
      (node (ref "LED17") (pin "3-GND") (pinfunction "GND_3-GND") (pintype "power_in"))
      (node (ref "LED18") (pin "3-GND") (pinfunction "GND_3-GND") (pintype "power_in"))
      (node (ref "LED19") (pin "3-GND") (pinfunction "GND_3-GND") (pintype "power_in"))
      (node (ref "LED2") (pin "3-GND") (pinfunction "GND_3-GND") (pintype "power_in"))
      (node (ref "LED20") (pin "3-GND") (pinfunction "GND_3-GND") (pintype "power_in"))
      (node (ref "LED21") (pin "3-GND") (pinfunction "GND_3-GND") (pintype "power_in"))
      (node (ref "LED22") (pin "3-GND") (pinfunction "GND_3-GND") (pintype "power_in"))
      (node (ref "LED23") (pin "3-GND") (pinfunction "GND_3-GND") (pintype "power_in"))
      (node (ref "LED24") (pin "3-GND") (pinfunction "GND_3-GND") (pintype "power_in"))
      (node (ref "LED25") (pin "3-GND") (pinfunction "GND_3-GND") (pintype "power_in"))
      (node (ref "LED26") (pin "3-GND") (pinfunction "GND_3-GND") (pintype "power_in"))
      (node (ref "LED27") (pin "3-GND") (pinfunction "GND_3-GND") (pintype "power_in"))
      (node (ref "LED28") (pin "3-GND") (pinfunction "GND_3-GND") (pintype "power_in"))
      (node (ref "LED29") (pin "3-GND") (pinfunction "GND_3-GND") (pintype "power_in"))
      (node (ref "LED3") (pin "3-GND") (pinfunction "GND_3-GND") (pintype "power_in"))
      (node (ref "LED30") (pin "3-GND") (pinfunction "GND_3-GND") (pintype "power_in"))
      (node (ref "LED31") (pin "3-GND") (pinfunction "GND_3-GND") (pintype "power_in"))
      (node (ref "LED32") (pin "3-GND") (pinfunction "GND_3-GND") (pintype "power_in"))
      (node (ref "LED33") (pin "3-GND") (pinfunction "GND_3-GND") (pintype "power_in"))
      (node (ref "LED34") (pin "3-GND") (pinfunction "GND_3-GND") (pintype "power_in"))
      (node (ref "LED35") (pin "3-GND") (pinfunction "GND_3-GND") (pintype "power_in"))
      (node (ref "LED36") (pin "3-GND") (pinfunction "GND_3-GND") (pintype "power_in"))
      (node (ref "LED37") (pin "3-GND") (pinfunction "GND_3-GND") (pintype "power_in"))
      (node (ref "LED38") (pin "3-GND") (pinfunction "GND_3-GND") (pintype "power_in"))
      (node (ref "LED39") (pin "3-GND") (pinfunction "GND_3-GND") (pintype "power_in"))
      (node (ref "LED4") (pin "3-GND") (pinfunction "GND_3-GND") (pintype "power_in"))
      (node (ref "LED40") (pin "3-GND") (pinfunction "GND_3-GND") (pintype "power_in"))
      (node (ref "LED41") (pin "3-GND") (pinfunction "GND_3-GND") (pintype "power_in"))
      (node (ref "LED42") (pin "3-GND") (pinfunction "GND_3-GND") (pintype "power_in"))
      (node (ref "LED43") (pin "3-GND") (pinfunction "GND_3-GND") (pintype "power_in"))
      (node (ref "LED44") (pin "3-GND") (pinfunction "GND_3-GND") (pintype "power_in"))
      (node (ref "LED45") (pin "3-GND") (pinfunction "GND_3-GND") (pintype "power_in"))
      (node (ref "LED46") (pin "3-GND") (pinfunction "GND_3-GND") (pintype "power_in"))
      (node (ref "LED47") (pin "3-GND") (pinfunction "GND_3-GND") (pintype "power_in"))
      (node (ref "LED48") (pin "3-GND") (pinfunction "GND_3-GND") (pintype "power_in"))
      (node (ref "LED49") (pin "3-GND") (pinfunction "GND_3-GND") (pintype "power_in"))
      (node (ref "LED5") (pin "3-GND") (pinfunction "GND_3-GND") (pintype "power_in"))
      (node (ref "LED50") (pin "3-GND") (pinfunction "GND_3-GND") (pintype "power_in"))
      (node (ref "LED51") (pin "3-GND") (pinfunction "GND_3-GND") (pintype "power_in"))
      (node (ref "LED52") (pin "3-GND") (pinfunction "GND_3-GND") (pintype "power_in"))
      (node (ref "LED53") (pin "3-GND") (pinfunction "GND_3-GND") (pintype "power_in"))
      (node (ref "LED54") (pin "3-GND") (pinfunction "GND_3-GND") (pintype "power_in"))
      (node (ref "LED55") (pin "3-GND") (pinfunction "GND_3-GND") (pintype "power_in"))
      (node (ref "LED56") (pin "3-GND") (pinfunction "GND_3-GND") (pintype "power_in"))
      (node (ref "LED57") (pin "3-GND") (pinfunction "GND_3-GND") (pintype "power_in"))
      (node (ref "LED58") (pin "3-GND") (pinfunction "GND_3-GND") (pintype "power_in"))
      (node (ref "LED59") (pin "3-GND") (pinfunction "GND_3-GND") (pintype "power_in"))
      (node (ref "LED6") (pin "3-GND") (pinfunction "GND_3-GND") (pintype "power_in"))
      (node (ref "LED60") (pin "3-GND") (pinfunction "GND_3-GND") (pintype "power_in"))
      (node (ref "LED61") (pin "3-GND") (pinfunction "GND_3-GND") (pintype "power_in"))
      (node (ref "LED62") (pin "3-GND") (pinfunction "GND_3-GND") (pintype "power_in"))
      (node (ref "LED63") (pin "3-GND") (pinfunction "GND_3-GND") (pintype "power_in"))
      (node (ref "LED64") (pin "3-GND") (pinfunction "GND_3-GND") (pintype "power_in"))
      (node (ref "LED65") (pin "3-GND") (pinfunction "GND_3-GND") (pintype "power_in"))
      (node (ref "LED66") (pin "3-GND") (pinfunction "GND_3-GND") (pintype "power_in"))
      (node (ref "LED7") (pin "3-GND") (pinfunction "GND_3-GND") (pintype "power_in"))
      (node (ref "LED8") (pin "3-GND") (pinfunction "GND_3-GND") (pintype "power_in"))
      (node (ref "LED9") (pin "3-GND") (pinfunction "GND_3-GND") (pintype "power_in"))
    )
    (net (code "5") (name "Net-(LED1-DI)") (class "Default")
      (node (ref "LED1") (pin "4-DIN") (pinfunction "DI_4-DIN") (pintype "input"))
      (node (ref "R1") (pin "2") (pinfunction "2_2") (pintype "passive"))
    )
    (net (code "6") (name "Net-(LED1-DO)") (class "Default")
      (node (ref "LED1") (pin "2-DOUT") (pinfunction "DO_2-DOUT") (pintype "output"))
      (node (ref "LED2") (pin "4-DIN") (pinfunction "DI_4-DIN") (pintype "input"))
    )
    (net (code "7") (name "Net-(LED2-DO)") (class "Default")
      (node (ref "LED2") (pin "2-DOUT") (pinfunction "DO_2-DOUT") (pintype "output"))
      (node (ref "LED3") (pin "4-DIN") (pinfunction "DI_4-DIN") (pintype "input"))
    )
    (net (code "8") (name "Net-(LED3-DO)") (class "Default")
      (node (ref "LED3") (pin "2-DOUT") (pinfunction "DO_2-DOUT") (pintype "output"))
      (node (ref "LED4") (pin "4-DIN") (pinfunction "DI_4-DIN") (pintype "input"))
    )
    (net (code "9") (name "Net-(LED4-DO)") (class "Default")
      (node (ref "LED4") (pin "2-DOUT") (pinfunction "DO_2-DOUT") (pintype "output"))
      (node (ref "LED5") (pin "4-DIN") (pinfunction "DI_4-DIN") (pintype "input"))
    )
    (net (code "10") (name "Net-(LED5-DO)") (class "Default")
      (node (ref "LED5") (pin "2-DOUT") (pinfunction "DO_2-DOUT") (pintype "output"))
      (node (ref "LED6") (pin "4-DIN") (pinfunction "DI_4-DIN") (pintype "input"))
    )
    (net (code "11") (name "Net-(LED6-DO)") (class "Default")
      (node (ref "LED6") (pin "2-DOUT") (pinfunction "DO_2-DOUT") (pintype "output"))
      (node (ref "LED7") (pin "4-DIN") (pinfunction "DI_4-DIN") (pintype "input"))
    )
    (net (code "12") (name "Net-(LED7-DO)") (class "Default")
      (node (ref "LED7") (pin "2-DOUT") (pinfunction "DO_2-DOUT") (pintype "output"))
      (node (ref "LED8") (pin "4-DIN") (pinfunction "DI_4-DIN") (pintype "input"))
    )
    (net (code "13") (name "Net-(LED8-DO)") (class "Default")
      (node (ref "LED8") (pin "2-DOUT") (pinfunction "DO_2-DOUT") (pintype "output"))
      (node (ref "LED9") (pin "4-DIN") (pinfunction "DI_4-DIN") (pintype "input"))
    )
    (net (code "14") (name "Net-(LED10-DI)") (class "Default")
      (node (ref "LED10") (pin "4-DIN") (pinfunction "DI_4-DIN") (pintype "input"))
      (node (ref "LED9") (pin "2-DOUT") (pinfunction "DO_2-DOUT") (pintype "output"))
    )
    (net (code "15") (name "Net-(LED10-DO)") (class "Default")
      (node (ref "LED10") (pin "2-DOUT") (pinfunction "DO_2-DOUT") (pintype "output"))
      (node (ref "LED11") (pin "4-DIN") (pinfunction "DI_4-DIN") (pintype "input"))
    )
    (net (code "16") (name "Net-(LED11-DO)") (class "Default")
      (node (ref "LED11") (pin "2-DOUT") (pinfunction "DO_2-DOUT") (pintype "output"))
      (node (ref "LED12") (pin "4-DIN") (pinfunction "DI_4-DIN") (pintype "input"))
    )
    (net (code "17") (name "Net-(LED12-DO)") (class "Default")
      (node (ref "LED12") (pin "2-DOUT") (pinfunction "DO_2-DOUT") (pintype "output"))
      (node (ref "LED13") (pin "4-DIN") (pinfunction "DI_4-DIN") (pintype "input"))
    )
    (net (code "18") (name "Net-(LED13-DO)") (class "Default")
      (node (ref "LED13") (pin "2-DOUT") (pinfunction "DO_2-DOUT") (pintype "output"))
      (node (ref "LED14") (pin "4-DIN") (pinfunction "DI_4-DIN") (pintype "input"))
    )
    (net (code "19") (name "Net-(LED14-DO)") (class "Default")
      (node (ref "LED14") (pin "2-DOUT") (pinfunction "DO_2-DOUT") (pintype "output"))
      (node (ref "LED15") (pin "4-DIN") (pinfunction "DI_4-DIN") (pintype "input"))
    )
    (net (code "20") (name "Net-(LED15-DO)") (class "Default")
      (node (ref "LED15") (pin "2-DOUT") (pinfunction "DO_2-DOUT") (pintype "output"))
      (node (ref "LED16") (pin "4-DIN") (pinfunction "DI_4-DIN") (pintype "input"))
    )
    (net (code "21") (name "Net-(LED16-DO)") (class "Default")
      (node (ref "LED16") (pin "2-DOUT") (pinfunction "DO_2-DOUT") (pintype "output"))
      (node (ref "LED17") (pin "4-DIN") (pinfunction "DI_4-DIN") (pintype "input"))
    )
    (net (code "22") (name "Net-(LED17-DO)") (class "Default")
      (node (ref "LED17") (pin "2-DOUT") (pinfunction "DO_2-DOUT") (pintype "output"))
      (node (ref "LED18") (pin "4-DIN") (pinfunction "DI_4-DIN") (pintype "input"))
    )
    (net (code "23") (name "Net-(LED18-DO)") (class "Default")
      (node (ref "LED18") (pin "2-DOUT") (pinfunction "DO_2-DOUT") (pintype "output"))
      (node (ref "LED19") (pin "4-DIN") (pinfunction "DI_4-DIN") (pintype "input"))
    )
    (net (code "24") (name "Net-(LED19-DO)") (class "Default")
      (node (ref "LED19") (pin "2-DOUT") (pinfunction "DO_2-DOUT") (pintype "output"))
      (node (ref "LED20") (pin "4-DIN") (pinfunction "DI_4-DIN") (pintype "input"))
    )
    (net (code "25") (name "Net-(LED20-DO)") (class "Default")
      (node (ref "LED20") (pin "2-DOUT") (pinfunction "DO_2-DOUT") (pintype "output"))
      (node (ref "LED21") (pin "4-DIN") (pinfunction "DI_4-DIN") (pintype "input"))
    )
    (net (code "26") (name "Net-(LED21-DO)") (class "Default")
      (node (ref "LED21") (pin "2-DOUT") (pinfunction "DO_2-DOUT") (pintype "output"))
      (node (ref "LED22") (pin "4-DIN") (pinfunction "DI_4-DIN") (pintype "input"))
    )
    (net (code "27") (name "Net-(LED22-DO)") (class "Default")
      (node (ref "LED22") (pin "2-DOUT") (pinfunction "DO_2-DOUT") (pintype "output"))
      (node (ref "LED23") (pin "4-DIN") (pinfunction "DI_4-DIN") (pintype "input"))
    )
    (net (code "28") (name "Net-(LED23-DO)") (class "Default")
      (node (ref "LED23") (pin "2-DOUT") (pinfunction "DO_2-DOUT") (pintype "output"))
      (node (ref "LED24") (pin "4-DIN") (pinfunction "DI_4-DIN") (pintype "input"))
    )
    (net (code "29") (name "Net-(LED24-DO)") (class "Default")
      (node (ref "LED24") (pin "2-DOUT") (pinfunction "DO_2-DOUT") (pintype "output"))
      (node (ref "LED25") (pin "4-DIN") (pinfunction "DI_4-DIN") (pintype "input"))
    )
    (net (code "30") (name "Net-(LED25-DO)") (class "Default")
      (node (ref "LED25") (pin "2-DOUT") (pinfunction "DO_2-DOUT") (pintype "output"))
      (node (ref "LED26") (pin "4-DIN") (pinfunction "DI_4-DIN") (pintype "input"))
    )
    (net (code "31") (name "Net-(LED26-DO)") (class "Default")
      (node (ref "LED26") (pin "2-DOUT") (pinfunction "DO_2-DOUT") (pintype "output"))
      (node (ref "LED27") (pin "4-DIN") (pinfunction "DI_4-DIN") (pintype "input"))
    )
    (net (code "32") (name "Net-(LED27-DO)") (class "Default")
      (node (ref "LED27") (pin "2-DOUT") (pinfunction "DO_2-DOUT") (pintype "output"))
      (node (ref "LED28") (pin "4-DIN") (pinfunction "DI_4-DIN") (pintype "input"))
    )
    (net (code "33") (name "Net-(LED28-DO)") (class "Default")
      (node (ref "LED28") (pin "2-DOUT") (pinfunction "DO_2-DOUT") (pintype "output"))
      (node (ref "LED29") (pin "4-DIN") (pinfunction "DI_4-DIN") (pintype "input"))
    )
    (net (code "34") (name "Net-(LED29-DO)") (class "Default")
      (node (ref "LED29") (pin "2-DOUT") (pinfunction "DO_2-DOUT") (pintype "output"))
      (node (ref "LED30") (pin "4-DIN") (pinfunction "DI_4-DIN") (pintype "input"))
    )
    (net (code "35") (name "Net-(LED30-DO)") (class "Default")
      (node (ref "LED30") (pin "2-DOUT") (pinfunction "DO_2-DOUT") (pintype "output"))
      (node (ref "LED31") (pin "4-DIN") (pinfunction "DI_4-DIN") (pintype "input"))
    )
    (net (code "36") (name "Net-(LED31-DO)") (class "Default")
      (node (ref "LED31") (pin "2-DOUT") (pinfunction "DO_2-DOUT") (pintype "output"))
      (node (ref "LED32") (pin "4-DIN") (pinfunction "DI_4-DIN") (pintype "input"))
    )
    (net (code "37") (name "Net-(LED32-DO)") (class "Default")
      (node (ref "LED32") (pin "2-DOUT") (pinfunction "DO_2-DOUT") (pintype "output"))
      (node (ref "LED33") (pin "4-DIN") (pinfunction "DI_4-DIN") (pintype "input"))
    )
    (net (code "38") (name "Net-(LED33-DO)") (class "Default")
      (node (ref "LED33") (pin "2-DOUT") (pinfunction "DO_2-DOUT") (pintype "output"))
      (node (ref "LED34") (pin "4-DIN") (pinfunction "DI_4-DIN") (pintype "input"))
    )
    (net (code "39") (name "Net-(LED34-DO)") (class "Default")
      (node (ref "LED34") (pin "2-DOUT") (pinfunction "DO_2-DOUT") (pintype "output"))
      (node (ref "LED35") (pin "4-DIN") (pinfunction "DI_4-DIN") (pintype "input"))
    )
    (net (code "40") (name "Net-(LED35-DO)") (class "Default")
      (node (ref "LED35") (pin "2-DOUT") (pinfunction "DO_2-DOUT") (pintype "output"))
      (node (ref "LED36") (pin "4-DIN") (pinfunction "DI_4-DIN") (pintype "input"))
    )
    (net (code "41") (name "Net-(LED36-DO)") (class "Default")
      (node (ref "LED36") (pin "2-DOUT") (pinfunction "DO_2-DOUT") (pintype "output"))
      (node (ref "LED37") (pin "4-DIN") (pinfunction "DI_4-DIN") (pintype "input"))
    )
    (net (code "42") (name "Net-(LED37-DO)") (class "Default")
      (node (ref "LED37") (pin "2-DOUT") (pinfunction "DO_2-DOUT") (pintype "output"))
      (node (ref "LED38") (pin "4-DIN") (pinfunction "DI_4-DIN") (pintype "input"))
    )
    (net (code "43") (name "Net-(LED38-DO)") (class "Default")
      (node (ref "LED38") (pin "2-DOUT") (pinfunction "DO_2-DOUT") (pintype "output"))
      (node (ref "LED39") (pin "4-DIN") (pinfunction "DI_4-DIN") (pintype "input"))
    )
    (net (code "44") (name "Net-(LED39-DO)") (class "Default")
      (node (ref "LED39") (pin "2-DOUT") (pinfunction "DO_2-DOUT") (pintype "output"))
      (node (ref "LED40") (pin "4-DIN") (pinfunction "DI_4-DIN") (pintype "input"))
    )
    (net (code "45") (name "Net-(LED40-DO)") (class "Default")
      (node (ref "LED40") (pin "2-DOUT") (pinfunction "DO_2-DOUT") (pintype "output"))
      (node (ref "LED41") (pin "4-DIN") (pinfunction "DI_4-DIN") (pintype "input"))
    )
    (net (code "46") (name "Net-(LED41-DO)") (class "Default")
      (node (ref "LED41") (pin "2-DOUT") (pinfunction "DO_2-DOUT") (pintype "output"))
      (node (ref "LED42") (pin "4-DIN") (pinfunction "DI_4-DIN") (pintype "input"))
    )
    (net (code "47") (name "Net-(LED42-DO)") (class "Default")
      (node (ref "LED42") (pin "2-DOUT") (pinfunction "DO_2-DOUT") (pintype "output"))
      (node (ref "LED43") (pin "4-DIN") (pinfunction "DI_4-DIN") (pintype "input"))
    )
    (net (code "48") (name "Net-(LED43-DO)") (class "Default")
      (node (ref "LED43") (pin "2-DOUT") (pinfunction "DO_2-DOUT") (pintype "output"))
      (node (ref "LED44") (pin "4-DIN") (pinfunction "DI_4-DIN") (pintype "input"))
    )
    (net (code "49") (name "Net-(LED44-DO)") (class "Default")
      (node (ref "LED44") (pin "2-DOUT") (pinfunction "DO_2-DOUT") (pintype "output"))
      (node (ref "LED45") (pin "4-DIN") (pinfunction "DI_4-DIN") (pintype "input"))
    )
    (net (code "50") (name "Net-(LED45-DO)") (class "Default")
      (node (ref "LED45") (pin "2-DOUT") (pinfunction "DO_2-DOUT") (pintype "output"))
      (node (ref "LED46") (pin "4-DIN") (pinfunction "DI_4-DIN") (pintype "input"))
    )
    (net (code "51") (name "Net-(LED46-DO)") (class "Default")
      (node (ref "LED46") (pin "2-DOUT") (pinfunction "DO_2-DOUT") (pintype "output"))
      (node (ref "LED47") (pin "4-DIN") (pinfunction "DI_4-DIN") (pintype "input"))
    )
    (net (code "52") (name "Net-(LED47-DO)") (class "Default")
      (node (ref "LED47") (pin "2-DOUT") (pinfunction "DO_2-DOUT") (pintype "output"))
      (node (ref "LED48") (pin "4-DIN") (pinfunction "DI_4-DIN") (pintype "input"))
    )
    (net (code "53") (name "Net-(LED48-DO)") (class "Default")
      (node (ref "LED48") (pin "2-DOUT") (pinfunction "DO_2-DOUT") (pintype "output"))
      (node (ref "LED49") (pin "4-DIN") (pinfunction "DI_4-DIN") (pintype "input"))
    )
    (net (code "54") (name "Net-(LED49-DO)") (class "Default")
      (node (ref "LED49") (pin "2-DOUT") (pinfunction "DO_2-DOUT") (pintype "output"))
      (node (ref "LED50") (pin "4-DIN") (pinfunction "DI_4-DIN") (pintype "input"))
    )
    (net (code "55") (name "Net-(LED50-DO)") (class "Default")
      (node (ref "LED50") (pin "2-DOUT") (pinfunction "DO_2-DOUT") (pintype "output"))
      (node (ref "LED51") (pin "4-DIN") (pinfunction "DI_4-DIN") (pintype "input"))
    )
    (net (code "56") (name "Net-(LED51-DO)") (class "Default")
      (node (ref "LED51") (pin "2-DOUT") (pinfunction "DO_2-DOUT") (pintype "output"))
      (node (ref "LED52") (pin "4-DIN") (pinfunction "DI_4-DIN") (pintype "input"))
    )
    (net (code "57") (name "Net-(LED52-DO)") (class "Default")
      (node (ref "LED52") (pin "2-DOUT") (pinfunction "DO_2-DOUT") (pintype "output"))
      (node (ref "LED53") (pin "4-DIN") (pinfunction "DI_4-DIN") (pintype "input"))
    )
    (net (code "58") (name "Net-(LED53-DO)") (class "Default")
      (node (ref "LED53") (pin "2-DOUT") (pinfunction "DO_2-DOUT") (pintype "output"))
      (node (ref "LED54") (pin "4-DIN") (pinfunction "DI_4-DIN") (pintype "input"))
    )
    (net (code "59") (name "Net-(LED54-DO)") (class "Default")
      (node (ref "LED54") (pin "2-DOUT") (pinfunction "DO_2-DOUT") (pintype "output"))
      (node (ref "LED55") (pin "4-DIN") (pinfunction "DI_4-DIN") (pintype "input"))
    )
    (net (code "60") (name "Net-(LED55-DO)") (class "Default")
      (node (ref "LED55") (pin "2-DOUT") (pinfunction "DO_2-DOUT") (pintype "output"))
      (node (ref "LED56") (pin "4-DIN") (pinfunction "DI_4-DIN") (pintype "input"))
    )
    (net (code "61") (name "Net-(LED56-DO)") (class "Default")
      (node (ref "LED56") (pin "2-DOUT") (pinfunction "DO_2-DOUT") (pintype "output"))
      (node (ref "LED57") (pin "4-DIN") (pinfunction "DI_4-DIN") (pintype "input"))
    )
    (net (code "62") (name "Net-(LED57-DO)") (class "Default")
      (node (ref "LED57") (pin "2-DOUT") (pinfunction "DO_2-DOUT") (pintype "output"))
      (node (ref "LED58") (pin "4-DIN") (pinfunction "DI_4-DIN") (pintype "input"))
    )
    (net (code "63") (name "Net-(LED58-DO)") (class "Default")
      (node (ref "LED58") (pin "2-DOUT") (pinfunction "DO_2-DOUT") (pintype "output"))
      (node (ref "LED59") (pin "4-DIN") (pinfunction "DI_4-DIN") (pintype "input"))
    )
    (net (code "64") (name "Net-(LED59-DO)") (class "Default")
      (node (ref "LED59") (pin "2-DOUT") (pinfunction "DO_2-DOUT") (pintype "output"))
      (node (ref "LED60") (pin "4-DIN") (pinfunction "DI_4-DIN") (pintype "input"))
    )
    (net (code "65") (name "Net-(LED60-DO)") (class "Default")
      (node (ref "LED60") (pin "2-DOUT") (pinfunction "DO_2-DOUT") (pintype "output"))
      (node (ref "LED61") (pin "4-DIN") (pinfunction "DI_4-DIN") (pintype "input"))
    )
    (net (code "66") (name "Net-(LED61-DO)") (class "Default")
      (node (ref "LED61") (pin "2-DOUT") (pinfunction "DO_2-DOUT") (pintype "output"))
      (node (ref "LED62") (pin "4-DIN") (pinfunction "DI_4-DIN") (pintype "input"))
    )
    (net (code "67") (name "Net-(LED62-DO)") (class "Default")
      (node (ref "LED62") (pin "2-DOUT") (pinfunction "DO_2-DOUT") (pintype "output"))
      (node (ref "LED63") (pin "4-DIN") (pinfunction "DI_4-DIN") (pintype "input"))
    )
    (net (code "68") (name "Net-(LED63-DO)") (class "Default")
      (node (ref "LED63") (pin "2-DOUT") (pinfunction "DO_2-DOUT") (pintype "output"))
      (node (ref "LED64") (pin "4-DIN") (pinfunction "DI_4-DIN") (pintype "input"))
    )
    (net (code "69") (name "Net-(LED64-DO)") (class "Default")
      (node (ref "LED64") (pin "2-DOUT") (pinfunction "DO_2-DOUT") (pintype "output"))
      (node (ref "LED65") (pin "4-DIN") (pinfunction "DI_4-DIN") (pintype "input"))
    )
    (net (code "70") (name "Net-(LED65-DO)") (class "Default")
      (node (ref "LED65") (pin "2-DOUT") (pinfunction "DO_2-DOUT") (pintype "output"))
      (node (ref "LED66") (pin "4-DIN") (pinfunction "DI_4-DIN") (pintype "input"))
    )
  )
)
